# Blink_Blink_Beep_Boop.net
KiCad netlist of a schematic drawn in Altium Designer
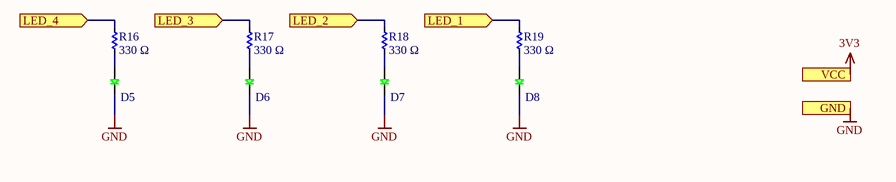
[diagram p0: Blink_Blink_Beep_Boop.SchDoc]

(export (version "E")
  (design (tool "Eeschema 10.0.6"))
  (components
    (comp (ref "D5")
      (value "LED_C503B-GCS-CB0C0781")
      (footprint "LED_TH_5MM")
      (description "LED GREEN CLEAR 5MM ROUND T/H")
      (fields
        (field (name "MANUFACTURER") "Cree")
        (field (name "MANUFACTURER PART NUMBER") "C503B-GCS-CB0C0781")
      )
      (libsource (lib "Stanford Student Space Initiative") (part "LED_C503B-GCS-CB0C0781"))
    )
    (comp (ref "D6")
      (value "LED_C503B-GCS-CB0C0781")
      (footprint "LED_TH_5MM")
      (description "LED GREEN CLEAR 5MM ROUND T/H")
      (fields
        (field (name "MANUFACTURER") "Cree")
        (field (name "MANUFACTURER PART NUMBER") "C503B-GCS-CB0C0781")
      )
      (libsource (lib "Stanford Student Space Initiative") (part "LED_C503B-GCS-CB0C0781"))
    )
    (comp (ref "D7")
      (value "LED_C503B-GCS-CB0C0781")
      (footprint "LED_TH_5MM")
      (description "LED GREEN CLEAR 5MM ROUND T/H")
      (fields
        (field (name "MANUFACTURER") "Cree")
        (field (name "MANUFACTURER PART NUMBER") "C503B-GCS-CB0C0781")
      )
      (libsource (lib "Stanford Student Space Initiative") (part "LED_C503B-GCS-CB0C0781"))
    )
    (comp (ref "D8")
      (value "LED_C503B-GCS-CB0C0781")
      (footprint "LED_TH_5MM")
      (description "LED GREEN CLEAR 5MM ROUND T/H")
      (fields
        (field (name "MANUFACTURER") "Cree")
        (field (name "MANUFACTURER PART NUMBER") "C503B-GCS-CB0C0781")
      )
      (libsource (lib "Stanford Student Space Initiative") (part "LED_C503B-GCS-CB0C0781"))
    )
    (comp (ref "R16")
      (value "311-330HRCT-ND")
      (footprint "R0603")
      (description "RES SMD 330 OHM 1% 1/10W 0603")
      (fields
        (field (name "RESISTANCE") "330 Ω")
        (field (name "MANUFACTURER PART NUMBER") "RC0603FR-07330RL")
        (field (name "MANUFACTURER") "Yageo")
      )
      (libsource (lib "Stanford Student Space Initiative") (part "__template_resistor"))
    )
    (comp (ref "R17")
      (value "311-330HRCT-ND")
      (footprint "R0603")
      (description "RES SMD 330 OHM 1% 1/10W 0603")
      (fields
        (field (name "RESISTANCE") "330 Ω")
        (field (name "MANUFACTURER PART NUMBER") "RC0603FR-07330RL")
        (field (name "MANUFACTURER") "Yageo")
      )
      (libsource (lib "Stanford Student Space Initiative") (part "__template_resistor"))
    )
    (comp (ref "R18")
      (value "311-330HRCT-ND")
      (footprint "R0603")
      (description "RES SMD 330 OHM 1% 1/10W 0603")
      (fields
        (field (name "RESISTANCE") "330 Ω")
        (field (name "MANUFACTURER PART NUMBER") "RC0603FR-07330RL")
        (field (name "MANUFACTURER") "Yageo")
      )
      (libsource (lib "Stanford Student Space Initiative") (part "__template_resistor"))
    )
    (comp (ref "R19")
      (value "311-330HRCT-ND")
      (footprint "R0603")
      (description "RES SMD 330 OHM 1% 1/10W 0603")
      (fields
        (field (name "RESISTANCE") "330 Ω")
        (field (name "MANUFACTURER PART NUMBER") "RC0603FR-07330RL")
        (field (name "MANUFACTURER") "Yageo")
      )
      (libsource (lib "Stanford Student Space Initiative") (part "__template_resistor"))
    )
  )
  (nets
    (net (code "1") (name "/LED_1") (class "Default")
      (node (ref "R19") (pin "2") (pinfunction "2_2") (pintype "passive"))
    )
    (net (code "2") (name "/LED_2") (class "Default")
      (node (ref "R18") (pin "2") (pinfunction "2_2") (pintype "passive"))
    )
    (net (code "3") (name "/LED_3") (class "Default")
      (node (ref "R17") (pin "2") (pinfunction "2_2") (pintype "passive"))
    )
    (net (code "4") (name "/LED_4") (class "Default")
      (node (ref "R16") (pin "2") (pinfunction "2_2") (pintype "passive"))
    )
    (net (code "6") (name "GND") (class "Default")
      (node (ref "D5") (pin "2") (pinfunction "K_2") (pintype "passive"))
      (node (ref "D6") (pin "2") (pinfunction "K_2") (pintype "passive"))
      (node (ref "D7") (pin "2") (pinfunction "K_2") (pintype "passive"))
      (node (ref "D8") (pin "2") (pinfunction "K_2") (pintype "passive"))
    )
    (net (code "7") (name "Net-(D5-A)") (class "Default")
      (node (ref "D5") (pin "1") (pinfunction "A_1") (pintype "passive"))
      (node (ref "R16") (pin "1") (pinfunction "1_1") (pintype "passive"))
    )
    (net (code "8") (name "Net-(D6-A)") (class "Default")
      (node (ref "D6") (pin "1") (pinfunction "A_1") (pintype "passive"))
      (node (ref "R17") (pin "1") (pinfunction "1_1") (pintype "passive"))
    )
    (net (code "9") (name "Net-(D7-A)") (class "Default")
      (node (ref "D7") (pin "1") (pinfunction "A_1") (pintype "passive"))
      (node (ref "R18") (pin "1") (pinfunction "1_1") (pintype "passive"))
    )
    (net (code "10") (name "Net-(D8-A)") (class "Default")
      (node (ref "D8") (pin "1") (pinfunction "A_1") (pintype "passive"))
      (node (ref "R19") (pin "1") (pinfunction "1_1") (pintype "passive"))
    )
  )
)
